# Schematic.net
KiCad netlist of a schematic drawn in EAGLE
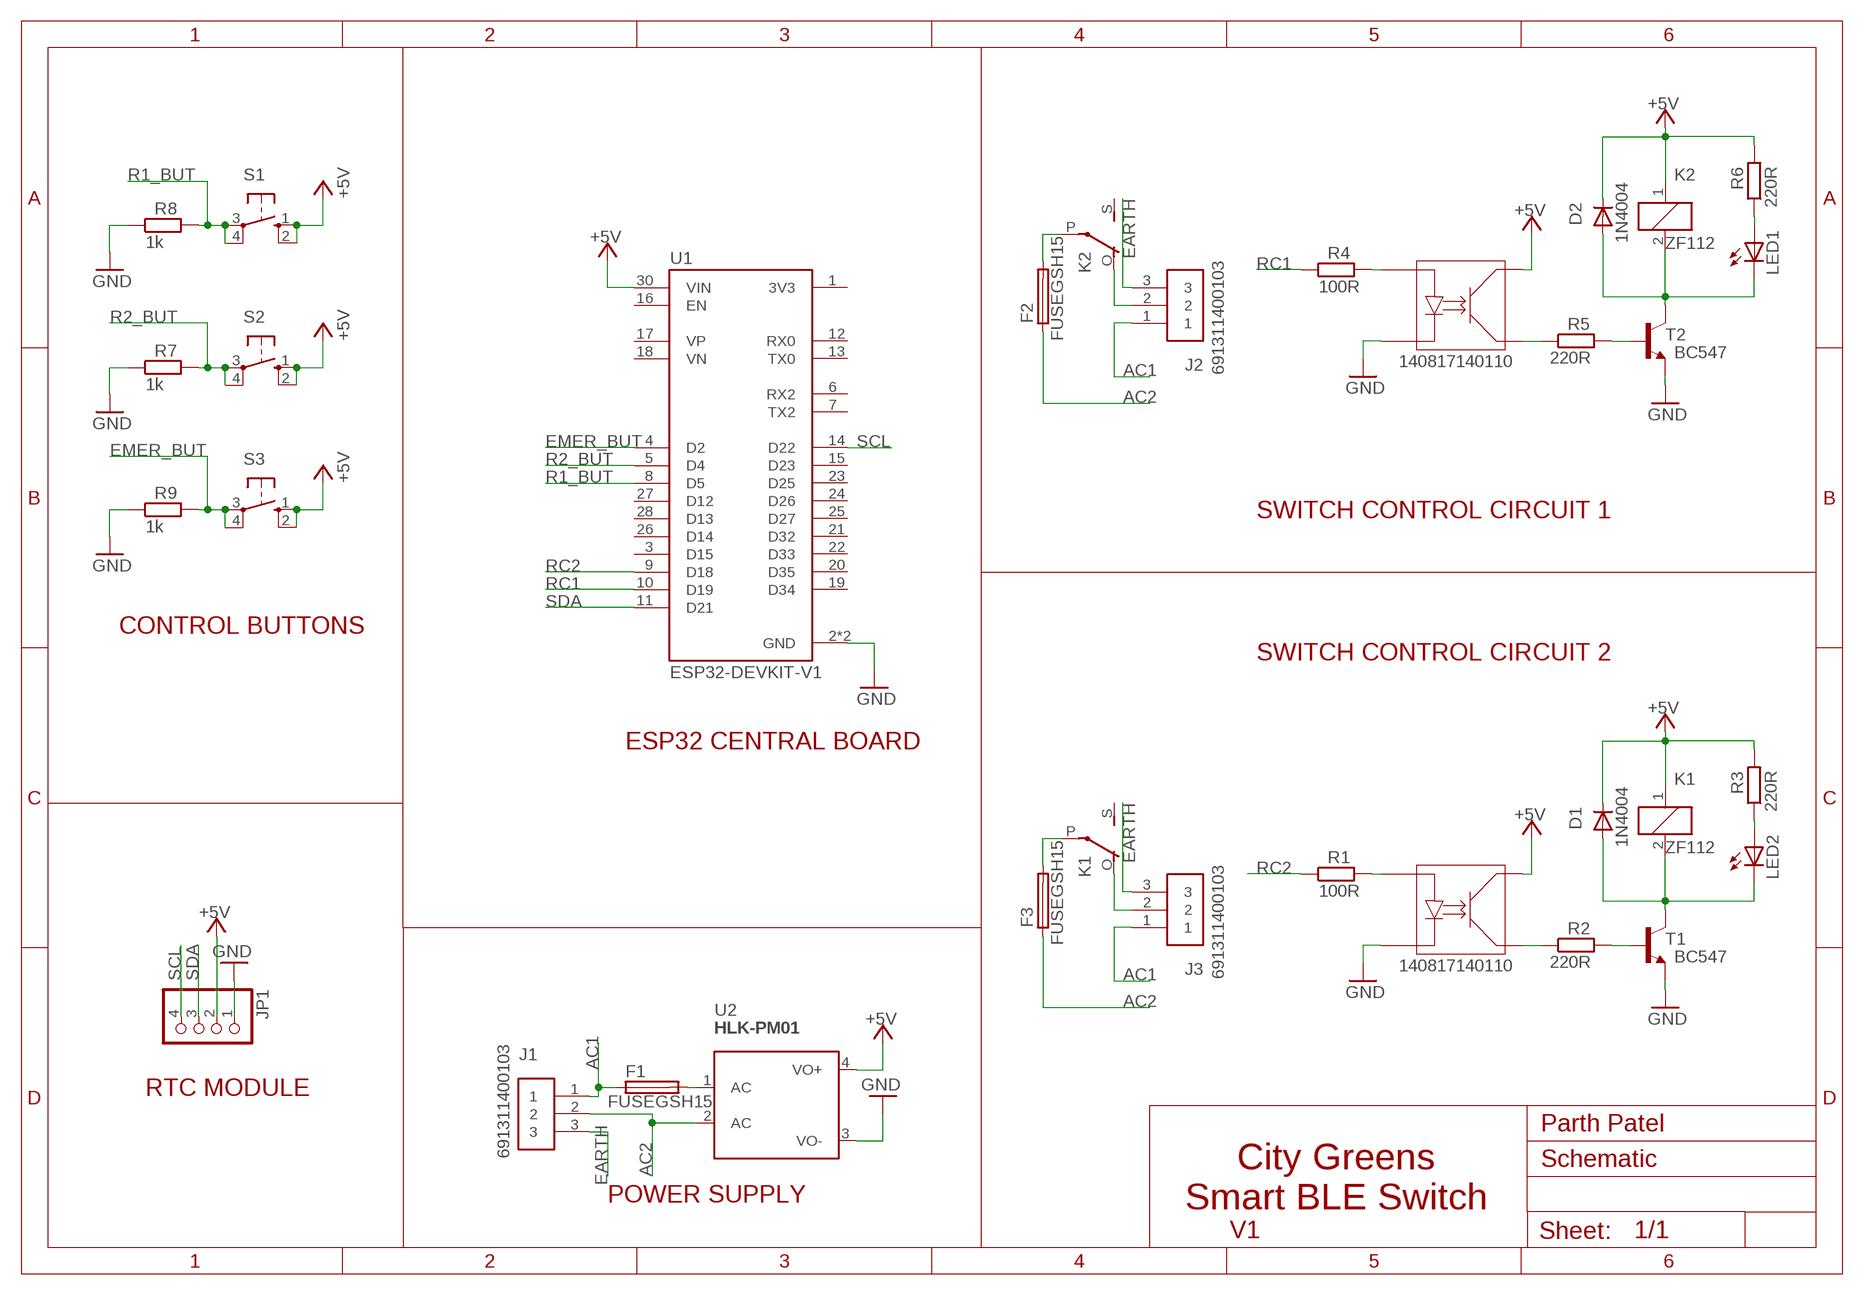
[diagram p0: schematic, sheet 1]

(export (version "E")
  (design (tool "Eeschema 10.0.6"))
  (components
    (comp (ref "D1")
      (value "1N4004")
      (footprint "eagle-import:DO41-10")
      (libsource (lib "eagle-import") (part "1N4004"))
    )
    (comp (ref "D2")
      (value "1N4004")
      (footprint "eagle-import:DO41-10")
      (libsource (lib "eagle-import") (part "1N4004"))
    )
    (comp (ref "F1")
      (value "FUSEGSH15")
      (footprint "eagle-import:GSH15")
      (libsource (lib "eagle-import") (part "FUSEGSH15"))
    )
    (comp (ref "F2")
      (value "FUSEGSH15")
      (footprint "eagle-import:GSH15")
      (libsource (lib "eagle-import") (part "FUSEGSH15"))
    )
    (comp (ref "F3")
      (value "FUSEGSH15")
      (footprint "eagle-import:GSH15")
      (libsource (lib "eagle-import") (part "FUSEGSH15"))
    )
    (comp (ref "J1")
      (value "691311400103")
      (footprint "eagle-import:TERMINALBLOCK_PLUGGABLE-3-7.62MM")
      (fields
        (field (name "DIGIKEY_PART_NO") "732-2824-ND")
        (field (name "MANUFACTURER") "WURTH ELEKTRONIK")
        (field (name "CREATED_BY") "PCBLayout.com")
      )
      (libsource (lib "eagle-import") (part "691311400103"))
    )
    (comp (ref "J2")
      (value "691311400103")
      (footprint "eagle-import:TERMINALBLOCK_PLUGGABLE-3-7.62MM")
      (fields
        (field (name "DIGIKEY_PART_NO") "732-2824-ND")
        (field (name "MANUFACTURER") "WURTH ELEKTRONIK")
        (field (name "CREATED_BY") "PCBLayout.com")
      )
      (libsource (lib "eagle-import") (part "691311400103"))
    )
    (comp (ref "J3")
      (value "691311400103")
      (footprint "eagle-import:TERMINALBLOCK_PLUGGABLE-3-7.62MM")
      (fields
        (field (name "DIGIKEY_PART_NO") "732-2824-ND")
        (field (name "MANUFACTURER") "WURTH ELEKTRONIK")
        (field (name "CREATED_BY") "PCBLayout.com")
      )
      (libsource (lib "eagle-import") (part "691311400103"))
    )
    (comp (ref "JP1")
      (value "PINHD-1X4")
      (footprint "eagle-import:1X04")
      (libsource (lib "eagle-import") (part "PINHD-1X4"))
    )
    (comp (ref "K1")
      (value "ZF112")
      (footprint "eagle-import:ZF112")
      (libsource (lib "eagle-import") (part "ZF112"))
    )
    (comp (ref "K2")
      (value "ZF112")
      (footprint "eagle-import:ZF112")
      (libsource (lib "eagle-import") (part "ZF112"))
    )
    (comp (ref "LED1")
      (value "LED3MM")
      (footprint "eagle-import:LED3MM")
      (libsource (lib "eagle-import") (part "LED3MM"))
    )
    (comp (ref "LED2")
      (value "LED3MM")
      (footprint "eagle-import:LED3MM")
      (libsource (lib "eagle-import") (part "LED3MM"))
    )
    (comp (ref "O1")
      (value "140817140110")
      (footprint "eagle-import:140817140110")
      (libsource (lib "eagle-import") (part "140817140110"))
    )
    (comp (ref "O2")
      (value "140817140110")
      (footprint "eagle-import:140817140110")
      (libsource (lib "eagle-import") (part "140817140110"))
    )
    (comp (ref "R1")
      (value "100R")
      (footprint "eagle-import:0207_10")
      (libsource (lib "eagle-import") (part "R-EU_0207/10"))
    )
    (comp (ref "R2")
      (value "220R")
      (footprint "eagle-import:0207_10")
      (libsource (lib "eagle-import") (part "R-EU_0207/10"))
    )
    (comp (ref "R3")
      (value "220R")
      (footprint "eagle-import:0207_10")
      (libsource (lib "eagle-import") (part "R-EU_0207/10"))
    )
    (comp (ref "R4")
      (value "100R")
      (footprint "eagle-import:0207_10")
      (libsource (lib "eagle-import") (part "R-EU_0207/10"))
    )
    (comp (ref "R5")
      (value "220R")
      (footprint "eagle-import:0207_10")
      (libsource (lib "eagle-import") (part "R-EU_0207/10"))
    )
    (comp (ref "R6")
      (value "220R")
      (footprint "eagle-import:0207_10")
      (libsource (lib "eagle-import") (part "R-EU_0207/10"))
    )
    (comp (ref "R7")
      (value "1k")
      (footprint "eagle-import:0207_10")
      (libsource (lib "eagle-import") (part "R-EU_0207/10"))
    )
    (comp (ref "R8")
      (value "1k")
      (footprint "eagle-import:0207_10")
      (libsource (lib "eagle-import") (part "R-EU_0207/10"))
    )
    (comp (ref "R9")
      (value "1k")
      (footprint "eagle-import:0207_10")
      (libsource (lib "eagle-import") (part "R-EU_0207/10"))
    )
    (comp (ref "S1")
      (value "10-XX")
      (footprint "eagle-import:B3F-10XX")
      (fields (field (name "MPN") "B3F-1000"))
      (libsource (lib "eagle-import") (part "10-XX"))
    )
    (comp (ref "S2")
      (value "10-XX")
      (footprint "eagle-import:B3F-10XX")
      (fields (field (name "MPN") "B3F-1000"))
      (libsource (lib "eagle-import") (part "10-XX"))
    )
    (comp (ref "S3")
      (value "10-XX")
      (footprint "eagle-import:B3F-10XX")
      (fields (field (name "MPN") "B3F-1000"))
      (libsource (lib "eagle-import") (part "10-XX"))
    )
    (comp (ref "T1")
      (value "BC547")
      (footprint "eagle-import:TO92")
      (libsource (lib "eagle-import") (part "-NPN-TO92"))
    )
    (comp (ref "T2")
      (value "BC547")
      (footprint "eagle-import:TO92")
      (libsource (lib "eagle-import") (part "-NPN-TO92"))
    )
    (comp (ref "U1")
      (value "ESP32-DEVKIT-V1")
      (footprint "eagle-import:MODULE_ESP32_DEVKIT_V1")
      (fields (field (name "MF") "Do it"))
      (libsource (lib "eagle-import") (part "ESP32-DEVKIT-V1"))
    )
    (comp (ref "U2")
      (value "HLK-PM01")
      (footprint "eagle-import:HLK-PM01")
      (fields (field (name "MF") "Hi-link") (field (name "MP") "hlk-pm01"))
      (libsource (lib "eagle-import") (part "HLK-PM01"))
    )
  )
  (nets
    (net (code "1") (name "+5V") (class "Default")
      (node (ref "D1") (pin "C") (pinfunction "C_C") (pintype "passive"))
      (node (ref "D2") (pin "C") (pinfunction "C_C") (pintype "passive"))
      (node (ref "JP1") (pin "2") (pinfunction "2_2") (pintype "passive"))
      (node (ref "K1") (pin "1") (pinfunction "1_1") (pintype "passive"))
      (node (ref "K2") (pin "1") (pinfunction "1_1") (pintype "passive"))
      (node (ref "O1") (pin "4") (pinfunction "4_4") (pintype "bidirectional"))
      (node (ref "O2") (pin "4") (pinfunction "4_4") (pintype "bidirectional"))
      (node (ref "R3") (pin "2") (pinfunction "2_2") (pintype "passive"))
      (node (ref "R6") (pin "2") (pinfunction "2_2") (pintype "passive"))
      (node (ref "S1") (pin "1") (pinfunction "S_1") (pintype "passive"))
      (node (ref "S1") (pin "2") (pinfunction "S1_2") (pintype "passive"))
      (node (ref "S2") (pin "1") (pinfunction "S_1") (pintype "passive"))
      (node (ref "S2") (pin "2") (pinfunction "S1_2") (pintype "passive"))
      (node (ref "S3") (pin "1") (pinfunction "S_1") (pintype "passive"))
      (node (ref "S3") (pin "2") (pinfunction "S1_2") (pintype "passive"))
      (node (ref "U1") (pin "30") (pinfunction "VIN_30") (pintype "input"))
      (node (ref "U2") (pin "4") (pinfunction "VO+_4") (pintype "bidirectional"))
    )
    (net (code "2") (name "/AC1") (class "Default")
      (node (ref "F1") (pin "1") (pinfunction "1_1") (pintype "passive"))
      (node (ref "J1") (pin "1") (pinfunction "1_1") (pintype "passive"))
      (node (ref "J2") (pin "1") (pinfunction "1_1") (pintype "passive"))
      (node (ref "J3") (pin "1") (pinfunction "1_1") (pintype "passive"))
    )
    (net (code "3") (name "/AC2") (class "Default")
      (node (ref "F2") (pin "1") (pinfunction "1_1") (pintype "passive"))
      (node (ref "F3") (pin "1") (pinfunction "1_1") (pintype "passive"))
      (node (ref "J1") (pin "2") (pinfunction "2_2") (pintype "passive"))
      (node (ref "U2") (pin "2") (pinfunction "AC_2") (pintype "bidirectional"))
    )
    (net (code "4") (name "/EARTH") (class "Default")
      (node (ref "J1") (pin "3") (pinfunction "3_3") (pintype "passive"))
      (node (ref "J2") (pin "3") (pinfunction "3_3") (pintype "passive"))
      (node (ref "J3") (pin "3") (pinfunction "3_3") (pintype "passive"))
    )
    (net (code "5") (name "/EMER_BUT") (class "Default")
      (node (ref "R9") (pin "2") (pinfunction "2_2") (pintype "passive"))
      (node (ref "S3") (pin "3") (pinfunction "P_3") (pintype "passive"))
      (node (ref "S3") (pin "4") (pinfunction "P1_4") (pintype "passive"))
      (node (ref "U1") (pin "4") (pinfunction "D2_4") (pintype "bidirectional"))
    )
    (net (code "6") (name "/R1_BUT") (class "Default")
      (node (ref "R8") (pin "2") (pinfunction "2_2") (pintype "passive"))
      (node (ref "S1") (pin "3") (pinfunction "P_3") (pintype "passive"))
      (node (ref "S1") (pin "4") (pinfunction "P1_4") (pintype "passive"))
      (node (ref "U1") (pin "8") (pinfunction "D5_8") (pintype "bidirectional"))
    )
    (net (code "7") (name "/R2_BUT") (class "Default")
      (node (ref "R7") (pin "2") (pinfunction "2_2") (pintype "passive"))
      (node (ref "S2") (pin "3") (pinfunction "P_3") (pintype "passive"))
      (node (ref "S2") (pin "4") (pinfunction "P1_4") (pintype "passive"))
      (node (ref "U1") (pin "5") (pinfunction "D4_5") (pintype "bidirectional"))
    )
    (net (code "8") (name "/RC1") (class "Default")
      (node (ref "R4") (pin "1") (pinfunction "1_1") (pintype "passive"))
      (node (ref "U1") (pin "10") (pinfunction "D19_10") (pintype "bidirectional"))
    )
    (net (code "9") (name "/RC2") (class "Default")
      (node (ref "R1") (pin "1") (pinfunction "1_1") (pintype "passive"))
      (node (ref "U1") (pin "9") (pinfunction "D18_9") (pintype "bidirectional"))
    )
    (net (code "10") (name "/SCL") (class "Default")
      (node (ref "JP1") (pin "4") (pinfunction "4_4") (pintype "passive"))
      (node (ref "U1") (pin "14") (pinfunction "D22_14") (pintype "bidirectional"))
    )
    (net (code "11") (name "/SDA") (class "Default")
      (node (ref "JP1") (pin "3") (pinfunction "3_3") (pintype "passive"))
      (node (ref "U1") (pin "11") (pinfunction "D21_11") (pintype "bidirectional"))
    )
    (net (code "12") (name "GND") (class "Default")
      (node (ref "JP1") (pin "1") (pinfunction "1_1") (pintype "passive"))
      (node (ref "O1") (pin "2") (pinfunction "2_2") (pintype "bidirectional"))
      (node (ref "O2") (pin "2") (pinfunction "2_2") (pintype "bidirectional"))
      (node (ref "R7") (pin "1") (pinfunction "1_1") (pintype "passive"))
      (node (ref "R8") (pin "1") (pinfunction "1_1") (pintype "passive"))
      (node (ref "R9") (pin "1") (pinfunction "1_1") (pintype "passive"))
      (node (ref "T1") (pin "1") (pinfunction "E_1") (pintype "passive"))
      (node (ref "T2") (pin "1") (pinfunction "E_1") (pintype "passive"))
      (node (ref "U1") (pin "2") (pinfunction "GND_2") (pintype "power_in"))
      (node (ref "U1") (pin "29") (pinfunction "GND_29") (pintype "power_in"))
      (node (ref "U2") (pin "3") (pinfunction "VO-_3") (pintype "bidirectional"))
    )
    (net (code "13") (name "Net-(F1-Pad2)") (class "Default")
      (node (ref "F1") (pin "2") (pinfunction "2_2") (pintype "passive"))
      (node (ref "U2") (pin "1") (pinfunction "AC_1") (pintype "bidirectional"))
    )
    (net (code "14") (name "Net-(F2-Pad2)") (class "Default")
      (node (ref "F2") (pin "2") (pinfunction "2_2") (pintype "passive"))
      (node (ref "K2") (pin "P") (pinfunction "P_P") (pintype "passive"))
    )
    (net (code "15") (name "Net-(F3-Pad2)") (class "Default")
      (node (ref "F3") (pin "2") (pinfunction "2_2") (pintype "passive"))
      (node (ref "K1") (pin "P") (pinfunction "P_P") (pintype "passive"))
    )
    (net (code "16") (name "Net-(J2-Pad2)") (class "Default")
      (node (ref "J2") (pin "2") (pinfunction "2_2") (pintype "passive"))
      (node (ref "K2") (pin "O") (pinfunction "O_O") (pintype "passive"))
    )
    (net (code "17") (name "Net-(J3-Pad2)") (class "Default")
      (node (ref "J3") (pin "2") (pinfunction "2_2") (pintype "passive"))
      (node (ref "K1") (pin "O") (pinfunction "O_O") (pintype "passive"))
    )
    (net (code "18") (name "Net-(LED1-C)") (class "Default")
      (node (ref "D2") (pin "A") (pinfunction "A_A") (pintype "passive"))
      (node (ref "K2") (pin "2") (pinfunction "2_2") (pintype "passive"))
      (node (ref "LED1") (pin "K") (pinfunction "C_K") (pintype "passive"))
      (node (ref "T2") (pin "3") (pinfunction "C_3") (pintype "passive"))
    )
    (net (code "19") (name "Net-(LED1-PadA)") (class "Default")
      (node (ref "LED1") (pin "A") (pinfunction "A_A") (pintype "passive"))
      (node (ref "R6") (pin "1") (pinfunction "1_1") (pintype "passive"))
    )
    (net (code "20") (name "Net-(LED2-C)") (class "Default")
      (node (ref "D1") (pin "A") (pinfunction "A_A") (pintype "passive"))
      (node (ref "K1") (pin "2") (pinfunction "2_2") (pintype "passive"))
      (node (ref "LED2") (pin "K") (pinfunction "C_K") (pintype "passive"))
      (node (ref "T1") (pin "3") (pinfunction "C_3") (pintype "passive"))
    )
    (net (code "21") (name "Net-(LED2-PadA)") (class "Default")
      (node (ref "LED2") (pin "A") (pinfunction "A_A") (pintype "passive"))
      (node (ref "R3") (pin "1") (pinfunction "1_1") (pintype "passive"))
    )
    (net (code "22") (name "Net-(O1-Pad1)") (class "Default")
      (node (ref "O1") (pin "1") (pinfunction "1_1") (pintype "bidirectional"))
      (node (ref "R1") (pin "2") (pinfunction "2_2") (pintype "passive"))
    )
    (net (code "23") (name "Net-(O1-Pad3)") (class "Default")
      (node (ref "O1") (pin "3") (pinfunction "3_3") (pintype "bidirectional"))
      (node (ref "R2") (pin "1") (pinfunction "1_1") (pintype "passive"))
    )
    (net (code "24") (name "Net-(O2-Pad1)") (class "Default")
      (node (ref "O2") (pin "1") (pinfunction "1_1") (pintype "bidirectional"))
      (node (ref "R4") (pin "2") (pinfunction "2_2") (pintype "passive"))
    )
    (net (code "25") (name "Net-(O2-Pad3)") (class "Default")
      (node (ref "O2") (pin "3") (pinfunction "3_3") (pintype "bidirectional"))
      (node (ref "R5") (pin "1") (pinfunction "1_1") (pintype "passive"))
    )
    (net (code "26") (name "Net-(T1-B)") (class "Default")
      (node (ref "R2") (pin "2") (pinfunction "2_2") (pintype "passive"))
      (node (ref "T1") (pin "2") (pinfunction "B_2") (pintype "passive"))
    )
    (net (code "27") (name "Net-(T2-B)") (class "Default")
      (node (ref "R5") (pin "2") (pinfunction "2_2") (pintype "passive"))
      (node (ref "T2") (pin "2") (pinfunction "B_2") (pintype "passive"))
    )
    (net (code "28") (name "unconnected-(K1-PadS)") (class "Default")
      (node (ref "K1") (pin "S") (pinfunction "S_S") (pintype "passive"))
    )
    (net (code "29") (name "unconnected-(K2-PadS)") (class "Default")
      (node (ref "K2") (pin "S") (pinfunction "S_S") (pintype "passive"))
    )
    (net (code "30") (name "unconnected-(U1-3V3-Pad1)") (class "Default")
      (node (ref "U1") (pin "1") (pinfunction "3V3_1") (pintype "output"))
    )
    (net (code "31") (name "unconnected-(U1-D12-Pad27)") (class "Default")
      (node (ref "U1") (pin "27") (pinfunction "D12_27") (pintype "bidirectional"))
    )
    (net (code "32") (name "unconnected-(U1-D13-Pad28)") (class "Default")
      (node (ref "U1") (pin "28") (pinfunction "D13_28") (pintype "bidirectional"))
    )
    (net (code "33") (name "unconnected-(U1-D14-Pad26)") (class "Default")
      (node (ref "U1") (pin "26") (pinfunction "D14_26") (pintype "bidirectional"))
    )
    (net (code "34") (name "unconnected-(U1-D15-Pad3)") (class "Default")
      (node (ref "U1") (pin "3") (pinfunction "D15_3") (pintype "bidirectional"))
    )
    (net (code "35") (name "unconnected-(U1-D23-Pad15)") (class "Default")
      (node (ref "U1") (pin "15") (pinfunction "D23_15") (pintype "bidirectional"))
    )
    (net (code "36") (name "unconnected-(U1-D25-Pad23)") (class "Default")
      (node (ref "U1") (pin "23") (pinfunction "D25_23") (pintype "bidirectional"))
    )
    (net (code "37") (name "unconnected-(U1-D26-Pad24)") (class "Default")
      (node (ref "U1") (pin "24") (pinfunction "D26_24") (pintype "bidirectional"))
    )
    (net (code "38") (name "unconnected-(U1-D27-Pad25)") (class "Default")
      (node (ref "U1") (pin "25") (pinfunction "D27_25") (pintype "bidirectional"))
    )
    (net (code "39") (name "unconnected-(U1-D32-Pad21)") (class "Default")
      (node (ref "U1") (pin "21") (pinfunction "D32_21") (pintype "bidirectional"))
    )
    (net (code "40") (name "unconnected-(U1-D33-Pad22)") (class "Default")
      (node (ref "U1") (pin "22") (pinfunction "D33_22") (pintype "bidirectional"))
    )
    (net (code "41") (name "unconnected-(U1-D34-Pad19)") (class "Default")
      (node (ref "U1") (pin "19") (pinfunction "D34_19") (pintype "bidirectional"))
    )
    (net (code "42") (name "unconnected-(U1-D35-Pad20)") (class "Default")
      (node (ref "U1") (pin "20") (pinfunction "D35_20") (pintype "bidirectional"))
    )
    (net (code "43") (name "unconnected-(U1-EN-Pad16)") (class "Default")
      (node (ref "U1") (pin "16") (pinfunction "EN_16") (pintype "input"))
    )
    (net (code "44") (name "unconnected-(U1-RX0-Pad12)") (class "Default")
      (node (ref "U1") (pin "12") (pinfunction "RX0_12") (pintype "input"))
    )
    (net (code "45") (name "unconnected-(U1-RX2-Pad6)") (class "Default")
      (node (ref "U1") (pin "6") (pinfunction "RX2_6") (pintype "input"))
    )
    (net (code "46") (name "unconnected-(U1-TX0-Pad13)") (class "Default")
      (node (ref "U1") (pin "13") (pinfunction "TX0_13") (pintype "output"))
    )
    (net (code "47") (name "unconnected-(U1-TX2-Pad7)") (class "Default")
      (node (ref "U1") (pin "7") (pinfunction "TX2_7") (pintype "output"))
    )
    (net (code "48") (name "unconnected-(U1-VN-Pad18)") (class "Default")
      (node (ref "U1") (pin "18") (pinfunction "VN_18") (pintype "bidirectional"))
    )
    (net (code "49") (name "unconnected-(U1-VP-Pad17)") (class "Default")
      (node (ref "U1") (pin "17") (pinfunction "VP_17") (pintype "bidirectional"))
    )
  )
)
